# Main_PCB.net
KiCad netlist of a schematic drawn in Altium Designer
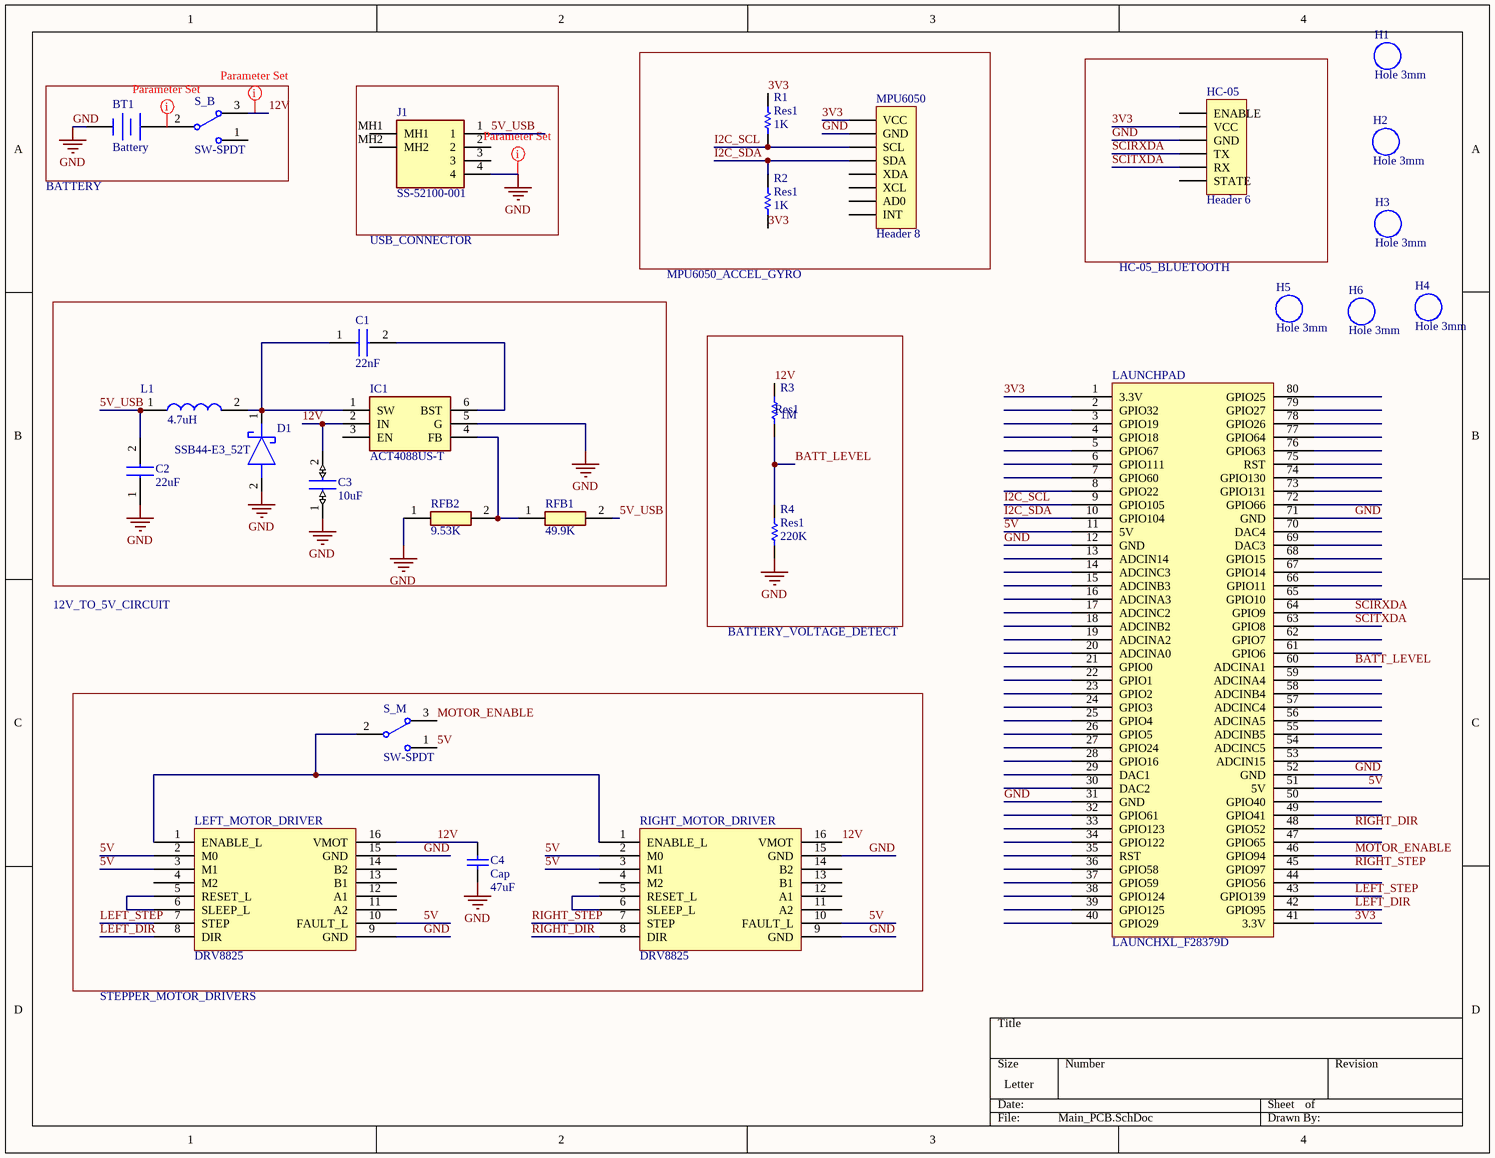
[diagram p0: Main_PCB.SchDoc]

(export (version "E")
  (design (tool "Eeschema 10.0.6"))
  (components
    (comp (ref "BT1")
      (value "Battery")
      (footprint "BATT_FP")
      (description "Multicell Battery")
      (fields (field (name "PUBLISHER") "Altium Limited"))
      (libsource (lib "Miscellaneous Devices") (part "Battery"))
    )
    (comp (ref "C1")
      (value "22nF")
      (footprint "SamacSys:CAPC2012X135N")
      (description "Capacitor")
      (fields (field (name "MANUFACTURER_PART_NUMBER") "VJ0805Y223JXAPW1BC"))
      (libsource (lib "*") (part "VJ0805Y223JXAPW1BC"))
    )
    (comp (ref "C2")
      (value "22uF")
      (footprint "SamacSys:CAPC2012X140N")
      (description "Capacitor")
      (fields (field (name "MANUFACTURER_PART_NUMBER") "08056D226MAT2A"))
      (libsource (lib "*") (part "08056D226MAT2A"))
    )
    (comp (ref "C3")
      (value "10uF")
      (footprint "SamacSys:CAPC2114X145N")
      (description "Capacitor")
      (fields (field (name "MANUFACTURER_PART_NUMBER") "TMK212BC6106KG-T"))
      (libsource (lib "SamacSys") (part "TMK212BC6106KG-T"))
    )
    (comp (ref "C4")
      (value "Cap")
      (footprint "RAD-0.3")
      (description "Capacitor")
      (fields (field (name "ALTIUM_VALUE") "47uF") (field (name "PUBLISHER") "Altium Limited"))
      (libsource (lib "Miscellaneous Devices") (part "Cap"))
    )
    (comp (ref "D1")
      (value "SSB44-E3_52T")
      (footprint "SamacSys:DIOM5436X244N")
      (description "Schottky Diode")
      (fields
        (field (name "MOUSER2 PART NUMBER") "625-SSB44-E3")
        (field (name "MANUFACTURER_PART_NUMBER") "SSB44-E3/52T")
      )
      (libsource (lib "*") (part "SSB44-E3_52T"))
    )
    (comp (ref "H1")
      (value "Hole 3mm")
      (footprint "Hole 3mm")
      (libsource (lib "ECE LIB new") (part "Hole 3mm"))
    )
    (comp (ref "H2")
      (value "Hole 3mm")
      (footprint "Hole 3mm")
      (libsource (lib "ECE LIB new") (part "Hole 3mm"))
    )
    (comp (ref "H3")
      (value "Hole 3mm")
      (footprint "Hole 3mm")
      (libsource (lib "ECE LIB new") (part "Hole 3mm"))
    )
    (comp (ref "H4")
      (value "Hole 3mm")
      (footprint "Hole 3mm")
      (libsource (lib "ECE LIB new") (part "Hole 3mm"))
    )
    (comp (ref "H5")
      (value "Hole 3mm")
      (footprint "Hole 3mm")
      (libsource (lib "ECE LIB new") (part "Hole 3mm"))
    )
    (comp (ref "H6")
      (value "Hole 3mm")
      (footprint "Hole 3mm")
      (libsource (lib "ECE LIB new") (part "Hole 3mm"))
    )
    (comp (ref "HC-05")
      (value "Header 6")
      (footprint "HDR1X6")
      (description "Header, 6-Pin")
      (fields (field (name "PUBLISHER") "Altium Limited"))
      (libsource (lib "Miscellaneous Connectors") (part "Header 6"))
    )
    (comp (ref "IC1")
      (value "ACT4088US-T")
      (footprint "SamacSys:SOT95P280X145-6N")
      (description "Integrated Circuit")
      (fields (field (name "MOUSER PART NUMBER") "107-ACT4088US-T"))
      (libsource (lib "*") (part "ACT4088US-T"))
    )
    (comp (ref "J1")
      (value "SS-52100-001")
      (footprint "SamacSys:SS52100001")
      (description "Connector")
      (libsource (lib "*") (part "SS-52100-001"))
    )
    (comp (ref "L1")
      (value "4.7uH")
      (footprint "SamacSys:INDC2520X120N")
      (description "Inductor")
      (fields (field (name "MANUFACTURER_PART_NUMBER") "TFM252012ALVA4R7MTAA"))
      (libsource (lib "*") (part "TFM252012ALVA4R7MTAA"))
    )
    (comp (ref "LAUNCHPAD")
      (value "LAUNCHXL_F28379D")
      (footprint "LAUNCH_PAD")
      (libsource (lib "Shida_Design2") (part "LAUNCHXL_F28379D"))
    )
    (comp (ref "LEFT_MOTOR_DRIVER")
      (value "DRV8825")
      (footprint "DRV8825_FP")
      (libsource (lib "Shida_Design2") (part "DRV8825"))
    )
    (comp (ref "MPU6050")
      (value "Header 8")
      (footprint "HDR1X8")
      (description "Header, 8-Pin")
      (fields (field (name "PUBLISHER") "Altium Limited"))
      (libsource (lib "Miscellaneous Connectors") (part "Header 8"))
    )
    (comp (ref "R1")
      (value "Res1")
      (footprint "AXIAL-0.3")
      (description "Resistor")
      (fields (field (name "ALTIUM_VALUE") "1K") (field (name "PUBLISHER") "Altium Limited"))
      (libsource (lib "Miscellaneous Devices") (part "Res1"))
    )
    (comp (ref "R2")
      (value "Res1")
      (footprint "AXIAL-0.3")
      (description "Resistor")
      (fields (field (name "ALTIUM_VALUE") "1K") (field (name "PUBLISHER") "Altium Limited"))
      (libsource (lib "Miscellaneous Devices") (part "Res1"))
    )
    (comp (ref "R3")
      (value "Res1")
      (footprint "AXIAL-0.3")
      (description "Resistor")
      (fields (field (name "ALTIUM_VALUE") "1M") (field (name "PUBLISHER") "Altium Limited"))
      (libsource (lib "Miscellaneous Devices") (part "Res1"))
    )
    (comp (ref "R4")
      (value "Res1")
      (footprint "AXIAL-0.3")
      (description "Resistor")
      (fields (field (name "ALTIUM_VALUE") "220K") (field (name "PUBLISHER") "Altium Limited"))
      (libsource (lib "Miscellaneous Devices") (part "Res1"))
    )
    (comp (ref "RFB1")
      (value "49.9K")
      (footprint "SamacSys:RESC2012X50N")
      (description "Resistor")
      (fields (field (name "MANUFACTURER_PART_NUMBER") "CRCW080549K9FKEA"))
      (libsource (lib "*") (part "CRCW080549K9FKEA"))
    )
    (comp (ref "RFB2")
      (value "9.53K")
      (footprint "SamacSys:RESC2012X50N")
      (description "Resistor")
      (fields
        (field (name "MOUSER2 PART NUMBER") "71-CRCW0805-9.53K-E3")
        (field (name "MANUFACTURER_PART_NUMBER") "CRCW08059K53FKEA")
      )
      (libsource (lib "*") (part "CRCW08059K53FKEA"))
    )
    (comp (ref "RIGHT_MOTOR_DRIVER")
      (value "DRV8825")
      (footprint "DRV8825_FP")
      (libsource (lib "Shida_Design2") (part "DRV8825"))
    )
    (comp (ref "S_B")
      (value "SW-SPDT")
      (footprint "SPDT_LARGE")
      (description "SPDT Subminiature Toggle Switch, Right Angle Mounting, Vertical Actuation")
      (fields (field (name "PUBLISHER") "Altium Limited"))
      (libsource (lib "ECE LIB new") (part "SW-SPDT"))
    )
    (comp (ref "S_M")
      (value "SW-SPDT")
      (footprint "SW DPST jameco")
      (description "SPDT Subminiature Toggle Switch, Right Angle Mounting, Vertical Actuation")
      (fields (field (name "PUBLISHER") "Altium Limited"))
      (libsource (lib "ECE LIB new") (part "SW-SPDT"))
    )
  )
  (nets
    (net (code "1") (name "/3V3") (class "Default")
      (node (ref "HC-05") (pin "2") (pinfunction "VCC_2") (pintype "passive"))
      (node (ref "LAUNCHPAD") (pin "1") (pinfunction "3.3V_1") (pintype "passive"))
      (node (ref "LAUNCHPAD") (pin "41") (pinfunction "3.3V_41") (pintype "passive"))
      (node (ref "MPU6050") (pin "1") (pinfunction "VCC_1") (pintype "passive"))
      (node (ref "R1") (pin "2") (pinfunction "2_2") (pintype "passive"))
      (node (ref "R2") (pin "1") (pinfunction "1_1") (pintype "passive"))
    )
    (net (code "2") (name "/5V") (class "Default")
      (node (ref "LAUNCHPAD") (pin "11") (pinfunction "5V_11") (pintype "passive"))
      (node (ref "LAUNCHPAD") (pin "51") (pinfunction "5V_51") (pintype "passive"))
      (node (ref "LEFT_MOTOR_DRIVER") (pin "10") (pinfunction "FAULT_L_10") (pintype "passive"))
      (node (ref "LEFT_MOTOR_DRIVER") (pin "2") (pinfunction "M0_2") (pintype "passive"))
      (node (ref "LEFT_MOTOR_DRIVER") (pin "3") (pinfunction "M1_3") (pintype "passive"))
      (node (ref "RIGHT_MOTOR_DRIVER") (pin "10") (pinfunction "FAULT_L_10") (pintype "passive"))
      (node (ref "RIGHT_MOTOR_DRIVER") (pin "2") (pinfunction "M0_2") (pintype "passive"))
      (node (ref "RIGHT_MOTOR_DRIVER") (pin "3") (pinfunction "M1_3") (pintype "passive"))
      (node (ref "S_M") (pin "1") (pinfunction "1_1") (pintype "passive"))
    )
    (net (code "3") (name "/5V_USB") (class "Default")
      (node (ref "C2") (pin "2") (pinfunction "C2_2") (pintype "passive"))
      (node (ref "J1") (pin "1") (pinfunction "1_1") (pintype "passive"))
      (node (ref "L1") (pin "1") (pinfunction "1_1") (pintype "passive"))
      (node (ref "RFB1") (pin "2") (pinfunction "2_2") (pintype "passive"))
    )
    (net (code "4") (name "/12V") (class "Default")
      (node (ref "C3") (pin "2") (pinfunction "2_2") (pintype "bidirectional"))
      (node (ref "C4") (pin "2") (pinfunction "2_2") (pintype "passive"))
      (node (ref "IC1") (pin "2") (pinfunction "IN_2") (pintype "passive"))
      (node (ref "LEFT_MOTOR_DRIVER") (pin "16") (pinfunction "VMOT_16") (pintype "passive"))
      (node (ref "R3") (pin "2") (pinfunction "2_2") (pintype "passive"))
      (node (ref "RIGHT_MOTOR_DRIVER") (pin "16") (pinfunction "VMOT_16") (pintype "passive"))
      (node (ref "S_B") (pin "3") (pinfunction "3_3") (pintype "passive"))
    )
    (net (code "5") (name "/BATT_LEVEL") (class "Default")
      (node (ref "LAUNCHPAD") (pin "60") (pinfunction "ADCINA1_60") (pintype "passive"))
      (node (ref "R3") (pin "1") (pinfunction "1_1") (pintype "passive"))
      (node (ref "R4") (pin "2") (pinfunction "2_2") (pintype "passive"))
    )
    (net (code "6") (name "/I2C_SCL") (class "Default")
      (node (ref "LAUNCHPAD") (pin "9") (pinfunction "GPIO105_9") (pintype "passive"))
      (node (ref "MPU6050") (pin "3") (pinfunction "SCL_3") (pintype "passive"))
      (node (ref "R1") (pin "1") (pinfunction "1_1") (pintype "passive"))
    )
    (net (code "7") (name "/I2C_SDA") (class "Default")
      (node (ref "LAUNCHPAD") (pin "10") (pinfunction "GPIO104_10") (pintype "passive"))
      (node (ref "MPU6050") (pin "4") (pinfunction "SDA_4") (pintype "passive"))
      (node (ref "R2") (pin "2") (pinfunction "2_2") (pintype "passive"))
    )
    (net (code "8") (name "/LEFT_DIR") (class "Default")
      (node (ref "LAUNCHPAD") (pin "42") (pinfunction "GPIO95_42") (pintype "passive"))
      (node (ref "LEFT_MOTOR_DRIVER") (pin "8") (pinfunction "DIR_8") (pintype "passive"))
    )
    (net (code "9") (name "/LEFT_STEP") (class "Default")
      (node (ref "LAUNCHPAD") (pin "43") (pinfunction "GPIO139_43") (pintype "passive"))
      (node (ref "LEFT_MOTOR_DRIVER") (pin "7") (pinfunction "STEP_7") (pintype "passive"))
    )
    (net (code "10") (name "/MOTOR_ENABLE") (class "Default")
      (node (ref "LAUNCHPAD") (pin "46") (pinfunction "GPIO94_46") (pintype "passive"))
      (node (ref "S_M") (pin "3") (pinfunction "3_3") (pintype "passive"))
    )
    (net (code "11") (name "/RIGHT_DIR") (class "Default")
      (node (ref "LAUNCHPAD") (pin "48") (pinfunction "GPIO52_48") (pintype "passive"))
      (node (ref "RIGHT_MOTOR_DRIVER") (pin "8") (pinfunction "DIR_8") (pintype "passive"))
    )
    (net (code "12") (name "/RIGHT_STEP") (class "Default")
      (node (ref "LAUNCHPAD") (pin "45") (pinfunction "GPIO97_45") (pintype "passive"))
      (node (ref "RIGHT_MOTOR_DRIVER") (pin "7") (pinfunction "STEP_7") (pintype "passive"))
    )
    (net (code "13") (name "/SCIRXDA") (class "Default")
      (node (ref "HC-05") (pin "4") (pinfunction "TX_4") (pintype "passive"))
      (node (ref "LAUNCHPAD") (pin "64") (pinfunction "GPIO9_64") (pintype "passive"))
    )
    (net (code "14") (name "/SCITXDA") (class "Default")
      (node (ref "HC-05") (pin "5") (pinfunction "RX_5") (pintype "passive"))
      (node (ref "LAUNCHPAD") (pin "63") (pinfunction "GPIO8_63") (pintype "passive"))
    )
    (net (code "15") (name "GND") (class "Default")
      (node (ref "BT1") (pin "2") (pinfunction "-_2") (pintype "passive"))
      (node (ref "C2") (pin "1") (pinfunction "C1_1") (pintype "passive"))
      (node (ref "C3") (pin "1") (pinfunction "1_1") (pintype "bidirectional"))
      (node (ref "C4") (pin "1") (pinfunction "1_1") (pintype "passive"))
      (node (ref "D1") (pin "2") (pinfunction "A_2") (pintype "passive"))
      (node (ref "HC-05") (pin "3") (pinfunction "GND_3") (pintype "passive"))
      (node (ref "IC1") (pin "5") (pinfunction "G_5") (pintype "passive"))
      (node (ref "J1") (pin "4") (pinfunction "4_4") (pintype "passive"))
      (node (ref "LAUNCHPAD") (pin "12") (pinfunction "GND_12") (pintype "passive"))
      (node (ref "LAUNCHPAD") (pin "31") (pinfunction "GND_31") (pintype "passive"))
      (node (ref "LAUNCHPAD") (pin "52") (pinfunction "GND_52") (pintype "passive"))
      (node (ref "LAUNCHPAD") (pin "71") (pinfunction "GND_71") (pintype "passive"))
      (node (ref "LEFT_MOTOR_DRIVER") (pin "15") (pinfunction "GND_15") (pintype "passive"))
      (node (ref "LEFT_MOTOR_DRIVER") (pin "9") (pinfunction "GND_9") (pintype "passive"))
      (node (ref "MPU6050") (pin "2") (pinfunction "GND_2") (pintype "passive"))
      (node (ref "R4") (pin "1") (pinfunction "1_1") (pintype "passive"))
      (node (ref "RFB2") (pin "1") (pinfunction "1_1") (pintype "passive"))
      (node (ref "RIGHT_MOTOR_DRIVER") (pin "15") (pinfunction "GND_15") (pintype "passive"))
      (node (ref "RIGHT_MOTOR_DRIVER") (pin "9") (pinfunction "GND_9") (pintype "passive"))
    )
    (net (code "16") (name "Net-(BT1-+)") (class "Default")
      (node (ref "BT1") (pin "1") (pinfunction "+_1") (pintype "passive"))
      (node (ref "S_B") (pin "2") (pinfunction "2_2") (pintype "passive"))
    )
    (net (code "17") (name "Net-(D1-K)") (class "Default")
      (node (ref "C1") (pin "1") (pinfunction "1_1") (pintype "passive"))
      (node (ref "D1") (pin "1") (pinfunction "K_1") (pintype "passive"))
      (node (ref "IC1") (pin "1") (pinfunction "SW_1") (pintype "passive"))
      (node (ref "L1") (pin "2") (pinfunction "2_2") (pintype "passive"))
    )
    (net (code "18") (name "Net-(IC1-BST)") (class "Default")
      (node (ref "C1") (pin "2") (pinfunction "2_2") (pintype "passive"))
      (node (ref "IC1") (pin "6") (pinfunction "BST_6") (pintype "passive"))
    )
    (net (code "19") (name "Net-(IC1-FB)") (class "Default")
      (node (ref "IC1") (pin "4") (pinfunction "FB_4") (pintype "passive"))
      (node (ref "RFB1") (pin "1") (pinfunction "1_1") (pintype "passive"))
      (node (ref "RFB2") (pin "2") (pinfunction "2_2") (pintype "passive"))
    )
    (net (code "20") (name "Net-(LEFT_MOTOR_DRIVER-ENABLE_L)") (class "Default")
      (node (ref "LEFT_MOTOR_DRIVER") (pin "1") (pinfunction "ENABLE_L_1") (pintype "passive"))
      (node (ref "RIGHT_MOTOR_DRIVER") (pin "1") (pinfunction "ENABLE_L_1") (pintype "passive"))
      (node (ref "S_M") (pin "2") (pinfunction "2_2") (pintype "passive"))
    )
    (net (code "21") (name "Net-(LEFT_MOTOR_DRIVER-RESET_L)") (class "Default")
      (node (ref "LEFT_MOTOR_DRIVER") (pin "5") (pinfunction "RESET_L_5") (pintype "passive"))
      (node (ref "LEFT_MOTOR_DRIVER") (pin "6") (pinfunction "SLEEP_L_6") (pintype "passive"))
    )
    (net (code "22") (name "Net-(RIGHT_MOTOR_DRIVER-RESET_L)") (class "Default")
      (node (ref "RIGHT_MOTOR_DRIVER") (pin "5") (pinfunction "RESET_L_5") (pintype "passive"))
      (node (ref "RIGHT_MOTOR_DRIVER") (pin "6") (pinfunction "SLEEP_L_6") (pintype "passive"))
    )
    (net (code "23") (name "unconnected-(HC-05-ENABLE-Pad1)") (class "Default")
      (node (ref "HC-05") (pin "1") (pinfunction "ENABLE_1") (pintype "passive"))
    )
    (net (code "24") (name "unconnected-(HC-05-STATE-Pad6)") (class "Default")
      (node (ref "HC-05") (pin "6") (pinfunction "STATE_6") (pintype "passive"))
    )
    (net (code "25") (name "unconnected-(IC1-EN-Pad3)") (class "Default")
      (node (ref "IC1") (pin "3") (pinfunction "EN_3") (pintype "passive"))
    )
    (net (code "26") (name "unconnected-(J1-Pad2)") (class "Default")
      (node (ref "J1") (pin "2") (pinfunction "2_2") (pintype "passive"))
    )
    (net (code "27") (name "unconnected-(J1-Pad3)") (class "Default")
      (node (ref "J1") (pin "3") (pinfunction "3_3") (pintype "passive"))
    )
    (net (code "28") (name "unconnected-(J1-PadMH1)") (class "Default")
      (node (ref "J1") (pin "MH1") (pinfunction "MH1_MH1") (pintype "passive"))
    )
    (net (code "29") (name "unconnected-(J1-PadMH2)") (class "Default")
      (node (ref "J1") (pin "MH2") (pinfunction "MH2_MH2") (pintype "passive"))
    )
    (net (code "30") (name "unconnected-(LAUNCHPAD-ADCIN14-Pad13)") (class "Default")
      (node (ref "LAUNCHPAD") (pin "13") (pinfunction "ADCIN14_13") (pintype "passive"))
    )
    (net (code "31") (name "unconnected-(LAUNCHPAD-ADCIN15-Pad53)") (class "Default")
      (node (ref "LAUNCHPAD") (pin "53") (pinfunction "ADCIN15_53") (pintype "passive"))
    )
    (net (code "32") (name "unconnected-(LAUNCHPAD-ADCINA0-Pad20)") (class "Default")
      (node (ref "LAUNCHPAD") (pin "20") (pinfunction "ADCINA0_20") (pintype "passive"))
    )
    (net (code "33") (name "unconnected-(LAUNCHPAD-ADCINA2-Pad19)") (class "Default")
      (node (ref "LAUNCHPAD") (pin "19") (pinfunction "ADCINA2_19") (pintype "passive"))
    )
    (net (code "34") (name "unconnected-(LAUNCHPAD-ADCINA3-Pad16)") (class "Default")
      (node (ref "LAUNCHPAD") (pin "16") (pinfunction "ADCINA3_16") (pintype "passive"))
    )
    (net (code "35") (name "unconnected-(LAUNCHPAD-ADCINA4-Pad59)") (class "Default")
      (node (ref "LAUNCHPAD") (pin "59") (pinfunction "ADCINA4_59") (pintype "passive"))
    )
    (net (code "36") (name "unconnected-(LAUNCHPAD-ADCINA5-Pad56)") (class "Default")
      (node (ref "LAUNCHPAD") (pin "56") (pinfunction "ADCINA5_56") (pintype "passive"))
    )
    (net (code "37") (name "unconnected-(LAUNCHPAD-ADCINB2-Pad18)") (class "Default")
      (node (ref "LAUNCHPAD") (pin "18") (pinfunction "ADCINB2_18") (pintype "passive"))
    )
    (net (code "38") (name "unconnected-(LAUNCHPAD-ADCINB3-Pad15)") (class "Default")
      (node (ref "LAUNCHPAD") (pin "15") (pinfunction "ADCINB3_15") (pintype "passive"))
    )
    (net (code "39") (name "unconnected-(LAUNCHPAD-ADCINB4-Pad58)") (class "Default")
      (node (ref "LAUNCHPAD") (pin "58") (pinfunction "ADCINB4_58") (pintype "passive"))
    )
    (net (code "40") (name "unconnected-(LAUNCHPAD-ADCINB5-Pad55)") (class "Default")
      (node (ref "LAUNCHPAD") (pin "55") (pinfunction "ADCINB5_55") (pintype "passive"))
    )
    (net (code "41") (name "unconnected-(LAUNCHPAD-ADCINC2-Pad17)") (class "Default")
      (node (ref "LAUNCHPAD") (pin "17") (pinfunction "ADCINC2_17") (pintype "passive"))
    )
    (net (code "42") (name "unconnected-(LAUNCHPAD-ADCINC3-Pad14)") (class "Default")
      (node (ref "LAUNCHPAD") (pin "14") (pinfunction "ADCINC3_14") (pintype "passive"))
    )
    (net (code "43") (name "unconnected-(LAUNCHPAD-ADCINC4-Pad57)") (class "Default")
      (node (ref "LAUNCHPAD") (pin "57") (pinfunction "ADCINC4_57") (pintype "passive"))
    )
    (net (code "44") (name "unconnected-(LAUNCHPAD-ADCINC5-Pad54)") (class "Default")
      (node (ref "LAUNCHPAD") (pin "54") (pinfunction "ADCINC5_54") (pintype "passive"))
    )
    (net (code "45") (name "unconnected-(LAUNCHPAD-DAC1-Pad29)") (class "Default")
      (node (ref "LAUNCHPAD") (pin "29") (pinfunction "DAC1_29") (pintype "passive"))
    )
    (net (code "46") (name "unconnected-(LAUNCHPAD-DAC2-Pad30)") (class "Default")
      (node (ref "LAUNCHPAD") (pin "30") (pinfunction "DAC2_30") (pintype "passive"))
    )
    (net (code "47") (name "unconnected-(LAUNCHPAD-DAC3-Pad69)") (class "Default")
      (node (ref "LAUNCHPAD") (pin "69") (pinfunction "DAC3_69") (pintype "passive"))
    )
    (net (code "48") (name "unconnected-(LAUNCHPAD-DAC4-Pad70)") (class "Default")
      (node (ref "LAUNCHPAD") (pin "70") (pinfunction "DAC4_70") (pintype "passive"))
    )
    (net (code "49") (name "unconnected-(LAUNCHPAD-GPIO0-Pad21)") (class "Default")
      (node (ref "LAUNCHPAD") (pin "21") (pinfunction "GPIO0_21") (pintype "passive"))
    )
    (net (code "50") (name "unconnected-(LAUNCHPAD-GPIO1-Pad22)") (class "Default")
      (node (ref "LAUNCHPAD") (pin "22") (pinfunction "GPIO1_22") (pintype "passive"))
    )
    (net (code "51") (name "unconnected-(LAUNCHPAD-GPIO2-Pad23)") (class "Default")
      (node (ref "LAUNCHPAD") (pin "23") (pinfunction "GPIO2_23") (pintype "passive"))
    )
    (net (code "52") (name "unconnected-(LAUNCHPAD-GPIO3-Pad24)") (class "Default")
      (node (ref "LAUNCHPAD") (pin "24") (pinfunction "GPIO3_24") (pintype "passive"))
    )
    (net (code "53") (name "unconnected-(LAUNCHPAD-GPIO4-Pad25)") (class "Default")
      (node (ref "LAUNCHPAD") (pin "25") (pinfunction "GPIO4_25") (pintype "passive"))
    )
    (net (code "54") (name "unconnected-(LAUNCHPAD-GPIO5-Pad26)") (class "Default")
      (node (ref "LAUNCHPAD") (pin "26") (pinfunction "GPIO5_26") (pintype "passive"))
    )
    (net (code "55") (name "unconnected-(LAUNCHPAD-GPIO6-Pad61)") (class "Default")
      (node (ref "LAUNCHPAD") (pin "61") (pinfunction "GPIO6_61") (pintype "passive"))
    )
    (net (code "56") (name "unconnected-(LAUNCHPAD-GPIO7-Pad62)") (class "Default")
      (node (ref "LAUNCHPAD") (pin "62") (pinfunction "GPIO7_62") (pintype "passive"))
    )
    (net (code "57") (name "unconnected-(LAUNCHPAD-GPIO10-Pad65)") (class "Default")
      (node (ref "LAUNCHPAD") (pin "65") (pinfunction "GPIO10_65") (pintype "passive"))
    )
    (net (code "58") (name "unconnected-(LAUNCHPAD-GPIO11-Pad66)") (class "Default")
      (node (ref "LAUNCHPAD") (pin "66") (pinfunction "GPIO11_66") (pintype "passive"))
    )
    (net (code "59") (name "unconnected-(LAUNCHPAD-GPIO14-Pad67)") (class "Default")
      (node (ref "LAUNCHPAD") (pin "67") (pinfunction "GPIO14_67") (pintype "passive"))
    )
    (net (code "60") (name "unconnected-(LAUNCHPAD-GPIO15-Pad68)") (class "Default")
      (node (ref "LAUNCHPAD") (pin "68") (pinfunction "GPIO15_68") (pintype "passive"))
    )
    (net (code "61") (name "unconnected-(LAUNCHPAD-GPIO16-Pad28)") (class "Default")
      (node (ref "LAUNCHPAD") (pin "28") (pinfunction "GPIO16_28") (pintype "passive"))
    )
    (net (code "62") (name "unconnected-(LAUNCHPAD-GPIO18-Pad4)") (class "Default")
      (node (ref "LAUNCHPAD") (pin "4") (pinfunction "GPIO18_4") (pintype "passive"))
    )
    (net (code "63") (name "unconnected-(LAUNCHPAD-GPIO19-Pad3)") (class "Default")
      (node (ref "LAUNCHPAD") (pin "3") (pinfunction "GPIO19_3") (pintype "passive"))
    )
    (net (code "64") (name "unconnected-(LAUNCHPAD-GPIO22-Pad8)") (class "Default")
      (node (ref "LAUNCHPAD") (pin "8") (pinfunction "GPIO22_8") (pintype "passive"))
    )
    (net (code "65") (name "unconnected-(LAUNCHPAD-GPIO24-Pad27)") (class "Default")
      (node (ref "LAUNCHPAD") (pin "27") (pinfunction "GPIO24_27") (pintype "passive"))
    )
    (net (code "66") (name "unconnected-(LAUNCHPAD-GPIO25-Pad80)") (class "Default")
      (node (ref "LAUNCHPAD") (pin "80") (pinfunction "GPIO25_80") (pintype "passive"))
    )
    (net (code "67") (name "unconnected-(LAUNCHPAD-GPIO26-Pad78)") (class "Default")
      (node (ref "LAUNCHPAD") (pin "78") (pinfunction "GPIO26_78") (pintype "passive"))
    )
    (net (code "68") (name "unconnected-(LAUNCHPAD-GPIO27-Pad79)") (class "Default")
      (node (ref "LAUNCHPAD") (pin "79") (pinfunction "GPIO27_79") (pintype "passive"))
    )
    (net (code "69") (name "unconnected-(LAUNCHPAD-GPIO29-Pad40)") (class "Default")
      (node (ref "LAUNCHPAD") (pin "40") (pinfunction "GPIO29_40") (pintype "passive"))
    )
    (net (code "70") (name "unconnected-(LAUNCHPAD-GPIO32-Pad2)") (class "Default")
      (node (ref "LAUNCHPAD") (pin "2") (pinfunction "GPIO32_2") (pintype "passive"))
    )
    (net (code "71") (name "unconnected-(LAUNCHPAD-GPIO40-Pad50)") (class "Default")
      (node (ref "LAUNCHPAD") (pin "50") (pinfunction "GPIO40_50") (pintype "passive"))
    )
    (net (code "72") (name "unconnected-(LAUNCHPAD-GPIO41-Pad49)") (class "Default")
      (node (ref "LAUNCHPAD") (pin "49") (pinfunction "GPIO41_49") (pintype "passive"))
    )
    (net (code "73") (name "unconnected-(LAUNCHPAD-GPIO56-Pad44)") (class "Default")
      (node (ref "LAUNCHPAD") (pin "44") (pinfunction "GPIO56_44") (pintype "passive"))
    )
    (net (code "74") (name "unconnected-(LAUNCHPAD-GPIO58-Pad36)") (class "Default")
      (node (ref "LAUNCHPAD") (pin "36") (pinfunction "GPIO58_36") (pintype "passive"))
    )
    (net (code "75") (name "unconnected-(LAUNCHPAD-GPIO59-Pad37)") (class "Default")
      (node (ref "LAUNCHPAD") (pin "37") (pinfunction "GPIO59_37") (pintype "passive"))
    )
    (net (code "76") (name "unconnected-(LAUNCHPAD-GPIO60-Pad7)") (class "Default")
      (node (ref "LAUNCHPAD") (pin "7") (pinfunction "GPIO60_7") (pintype "passive"))
    )
    (net (code "77") (name "unconnected-(LAUNCHPAD-GPIO61-Pad32)") (class "Default")
      (node (ref "LAUNCHPAD") (pin "32") (pinfunction "GPIO61_32") (pintype "passive"))
    )
    (net (code "78") (name "unconnected-(LAUNCHPAD-GPIO63-Pad76)") (class "Default")
      (node (ref "LAUNCHPAD") (pin "76") (pinfunction "GPIO63_76") (pintype "passive"))
    )
    (net (code "79") (name "unconnected-(LAUNCHPAD-GPIO64-Pad77)") (class "Default")
      (node (ref "LAUNCHPAD") (pin "77") (pinfunction "GPIO64_77") (pintype "passive"))
    )
    (net (code "80") (name "unconnected-(LAUNCHPAD-GPIO65-Pad47)") (class "Default")
      (node (ref "LAUNCHPAD") (pin "47") (pinfunction "GPIO65_47") (pintype "passive"))
    )
    (net (code "81") (name "unconnected-(LAUNCHPAD-GPIO66-Pad72)") (class "Default")
      (node (ref "LAUNCHPAD") (pin "72") (pinfunction "GPIO66_72") (pintype "passive"))
    )
    (net (code "82") (name "unconnected-(LAUNCHPAD-GPIO67-Pad5)") (class "Default")
      (node (ref "LAUNCHPAD") (pin "5") (pinfunction "GPIO67_5") (pintype "passive"))
    )
    (net (code "83") (name "unconnected-(LAUNCHPAD-GPIO111-Pad6)") (class "Default")
      (node (ref "LAUNCHPAD") (pin "6") (pinfunction "GPIO111_6") (pintype "passive"))
    )
    (net (code "84") (name "unconnected-(LAUNCHPAD-GPIO122-Pad34)") (class "Default")
      (node (ref "LAUNCHPAD") (pin "34") (pinfunction "GPIO122_34") (pintype "passive"))
    )
    (net (code "85") (name "unconnected-(LAUNCHPAD-GPIO123-Pad33)") (class "Default")
      (node (ref "LAUNCHPAD") (pin "33") (pinfunction "GPIO123_33") (pintype "passive"))
    )
    (net (code "86") (name "unconnected-(LAUNCHPAD-GPIO124-Pad38)") (class "Default")
      (node (ref "LAUNCHPAD") (pin "38") (pinfunction "GPIO124_38") (pintype "passive"))
    )
    (net (code "87") (name "unconnected-(LAUNCHPAD-GPIO125-Pad39)") (class "Default")
      (node (ref "LAUNCHPAD") (pin "39") (pinfunction "GPIO125_39") (pintype "passive"))
    )
    (net (code "88") (name "unconnected-(LAUNCHPAD-GPIO130-Pad74)") (class "Default")
      (node (ref "LAUNCHPAD") (pin "74") (pinfunction "GPIO130_74") (pintype "passive"))
    )
    (net (code "89") (name "unconnected-(LAUNCHPAD-GPIO131-Pad73)") (class "Default")
      (node (ref "LAUNCHPAD") (pin "73") (pinfunction "GPIO131_73") (pintype "passive"))
    )
    (net (code "90") (name "unconnected-(LAUNCHPAD-RST-Pad35)") (class "Default")
      (node (ref "LAUNCHPAD") (pin "35") (pinfunction "RST_35") (pintype "passive"))
    )
    (net (code "91") (name "unconnected-(LAUNCHPAD-RST-Pad75)") (class "Default")
      (node (ref "LAUNCHPAD") (pin "75") (pinfunction "RST_75") (pintype "passive"))
    )
    (net (code "92") (name "unconnected-(LEFT_MOTOR_DRIVER-A1-Pad12)") (class "Default")
      (node (ref "LEFT_MOTOR_DRIVER") (pin "12") (pinfunction "A1_12") (pintype "passive"))
    )
    (net (code "93") (name "unconnected-(LEFT_MOTOR_DRIVER-A2-Pad11)") (class "Default")
      (node (ref "LEFT_MOTOR_DRIVER") (pin "11") (pinfunction "A2_11") (pintype "passive"))
    )
    (net (code "94") (name "unconnected-(LEFT_MOTOR_DRIVER-B1-Pad13)") (class "Default")
      (node (ref "LEFT_MOTOR_DRIVER") (pin "13") (pinfunction "B1_13") (pintype "passive"))
    )
    (net (code "95") (name "unconnected-(LEFT_MOTOR_DRIVER-B2-Pad14)") (class "Default")
      (node (ref "LEFT_MOTOR_DRIVER") (pin "14") (pinfunction "B2_14") (pintype "passive"))
    )
    (net (code "96") (name "unconnected-(LEFT_MOTOR_DRIVER-M2-Pad4)") (class "Default")
      (node (ref "LEFT_MOTOR_DRIVER") (pin "4") (pinfunction "M2_4") (pintype "passive"))
    )
    (net (code "97") (name "unconnected-(MPU6050-AD0-Pad7)") (class "Default")
      (node (ref "MPU6050") (pin "7") (pinfunction "AD0_7") (pintype "passive"))
    )
    (net (code "98") (name "unconnected-(MPU6050-INT-Pad8)") (class "Default")
      (node (ref "MPU6050") (pin "8") (pinfunction "INT_8") (pintype "passive"))
    )
    (net (code "99") (name "unconnected-(MPU6050-XCL-Pad6)") (class "Default")
      (node (ref "MPU6050") (pin "6") (pinfunction "XCL_6") (pintype "passive"))
    )
    (net (code "100") (name "unconnected-(MPU6050-XDA-Pad5)") (class "Default")
      (node (ref "MPU6050") (pin "5") (pinfunction "XDA_5") (pintype "passive"))
    )
    (net (code "101") (name "unconnected-(RIGHT_MOTOR_DRIVER-A1-Pad12)") (class "Default")
      (node (ref "RIGHT_MOTOR_DRIVER") (pin "12") (pinfunction "A1_12") (pintype "passive"))
    )
    (net (code "102") (name "unconnected-(RIGHT_MOTOR_DRIVER-A2-Pad11)") (class "Default")
      (node (ref "RIGHT_MOTOR_DRIVER") (pin "11") (pinfunction "A2_11") (pintype "passive"))
    )
    (net (code "103") (name "unconnected-(RIGHT_MOTOR_DRIVER-B1-Pad13)") (class "Default")
      (node (ref "RIGHT_MOTOR_DRIVER") (pin "13") (pinfunction "B1_13") (pintype "passive"))
    )
    (net (code "104") (name "unconnected-(RIGHT_MOTOR_DRIVER-B2-Pad14)") (class "Default")
      (node (ref "RIGHT_MOTOR_DRIVER") (pin "14") (pinfunction "B2_14") (pintype "passive"))
    )
    (net (code "105") (name "unconnected-(RIGHT_MOTOR_DRIVER-M2-Pad4)") (class "Default")
      (node (ref "RIGHT_MOTOR_DRIVER") (pin "4") (pinfunction "M2_4") (pintype "passive"))
    )
    (net (code "106") (name "unconnected-(S_B-Pad1)") (class "Default")
      (node (ref "S_B") (pin "1") (pinfunction "1_1") (pintype "passive"))
    )
  )
)
